# module_af.net
KiCad netlist of a schematic drawn in EAGLE
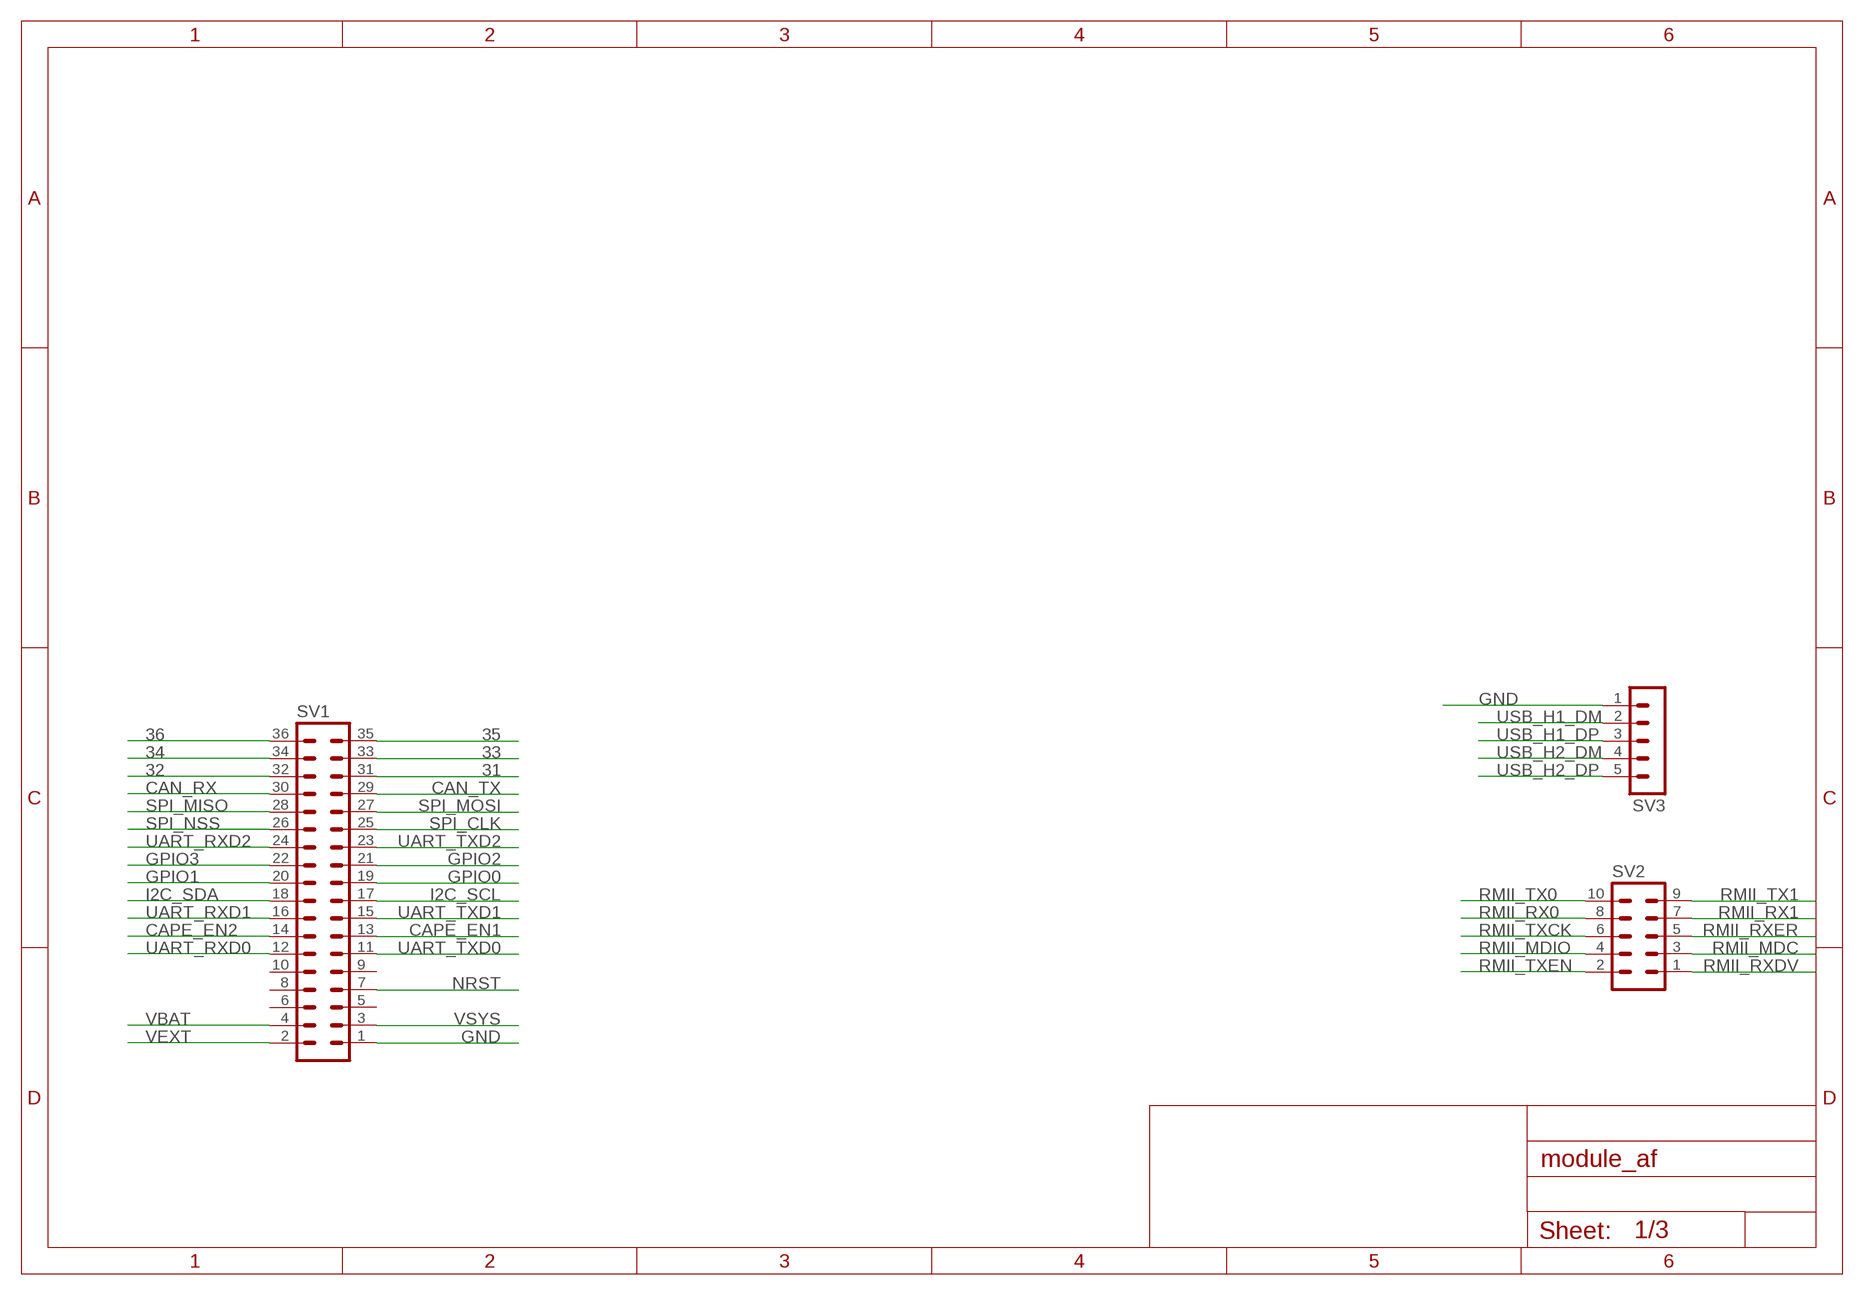
[diagram p0: schematic, sheet 1]
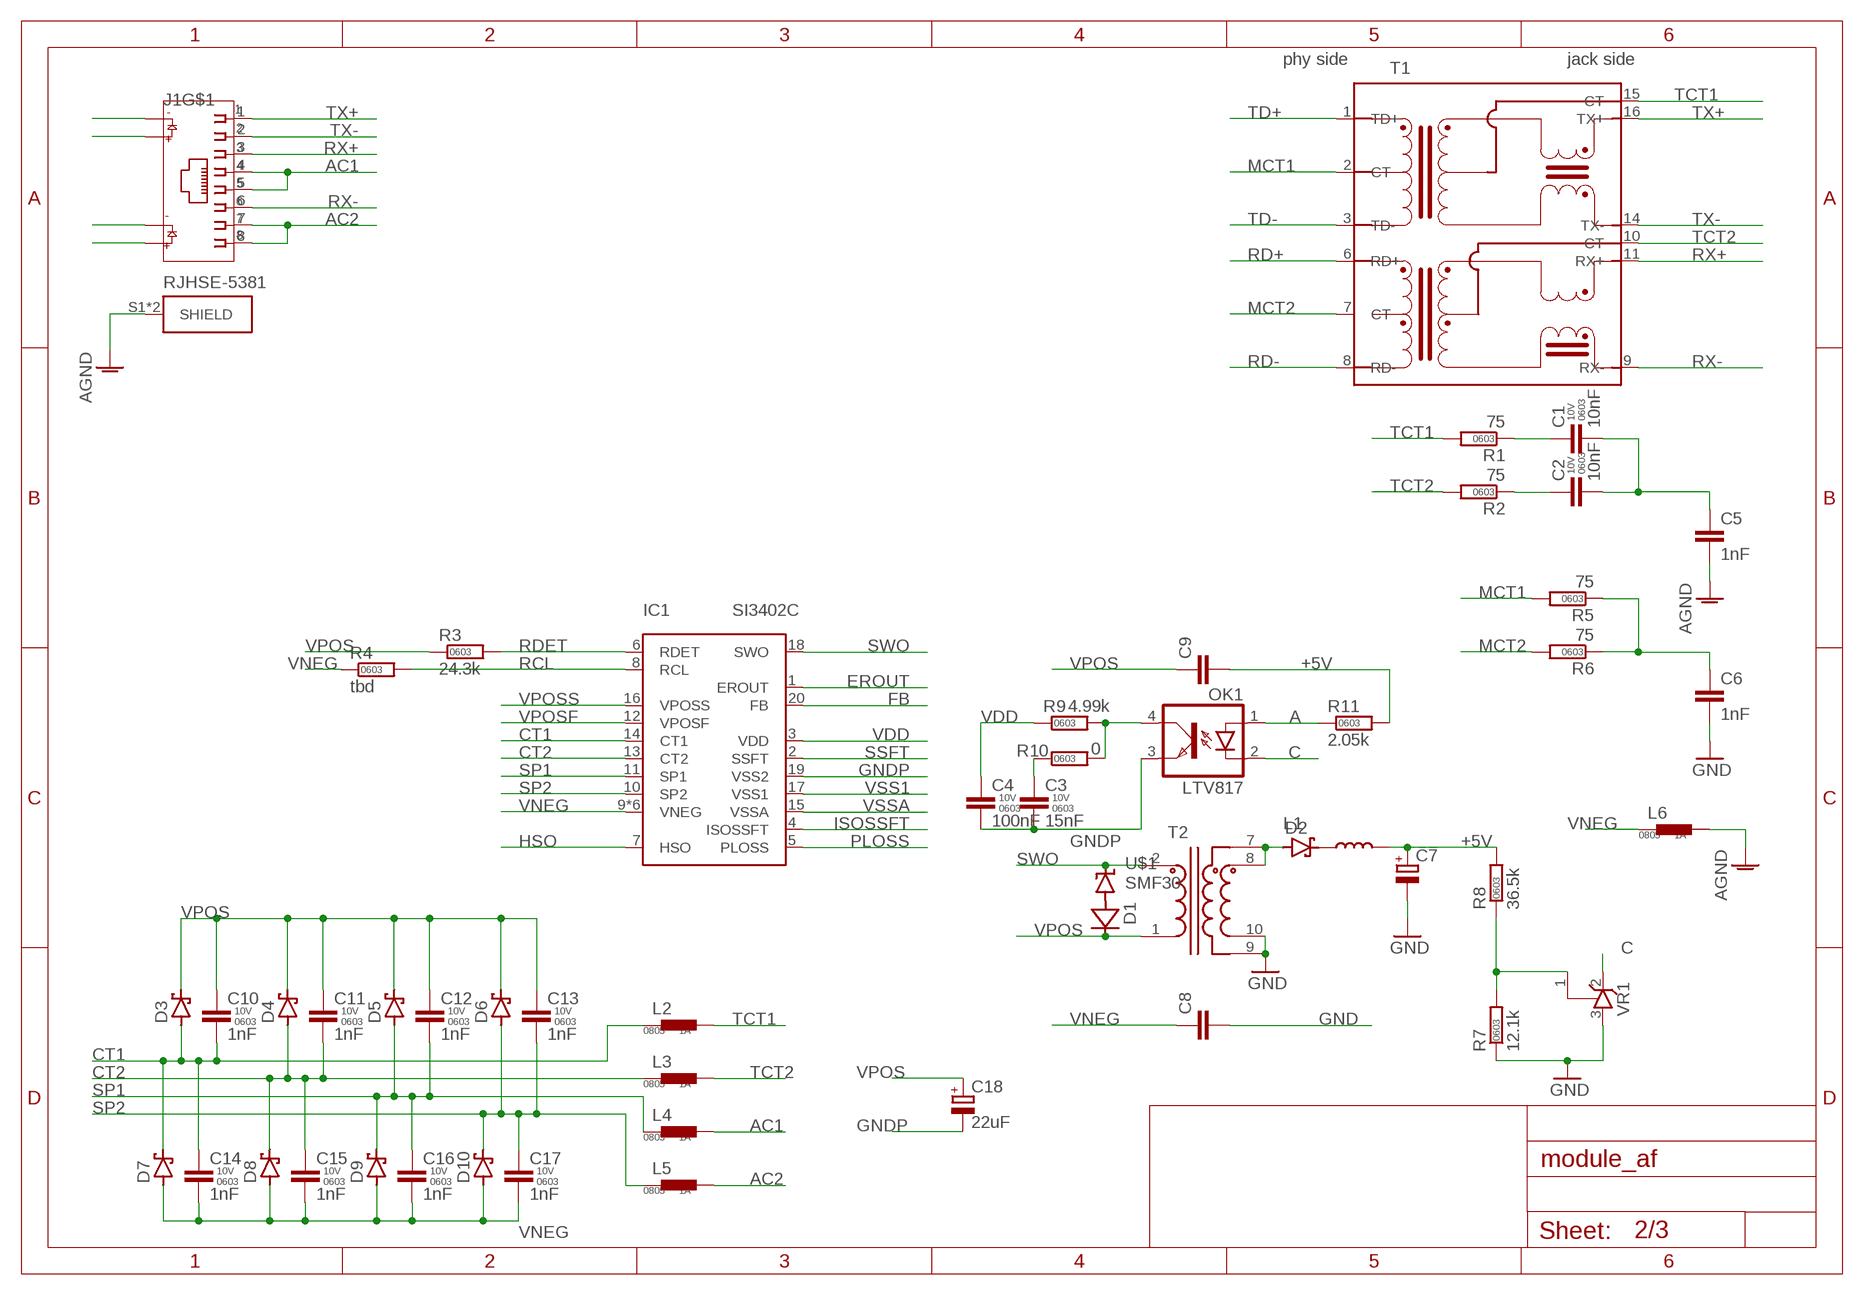
[diagram p1: schematic, sheet 2]
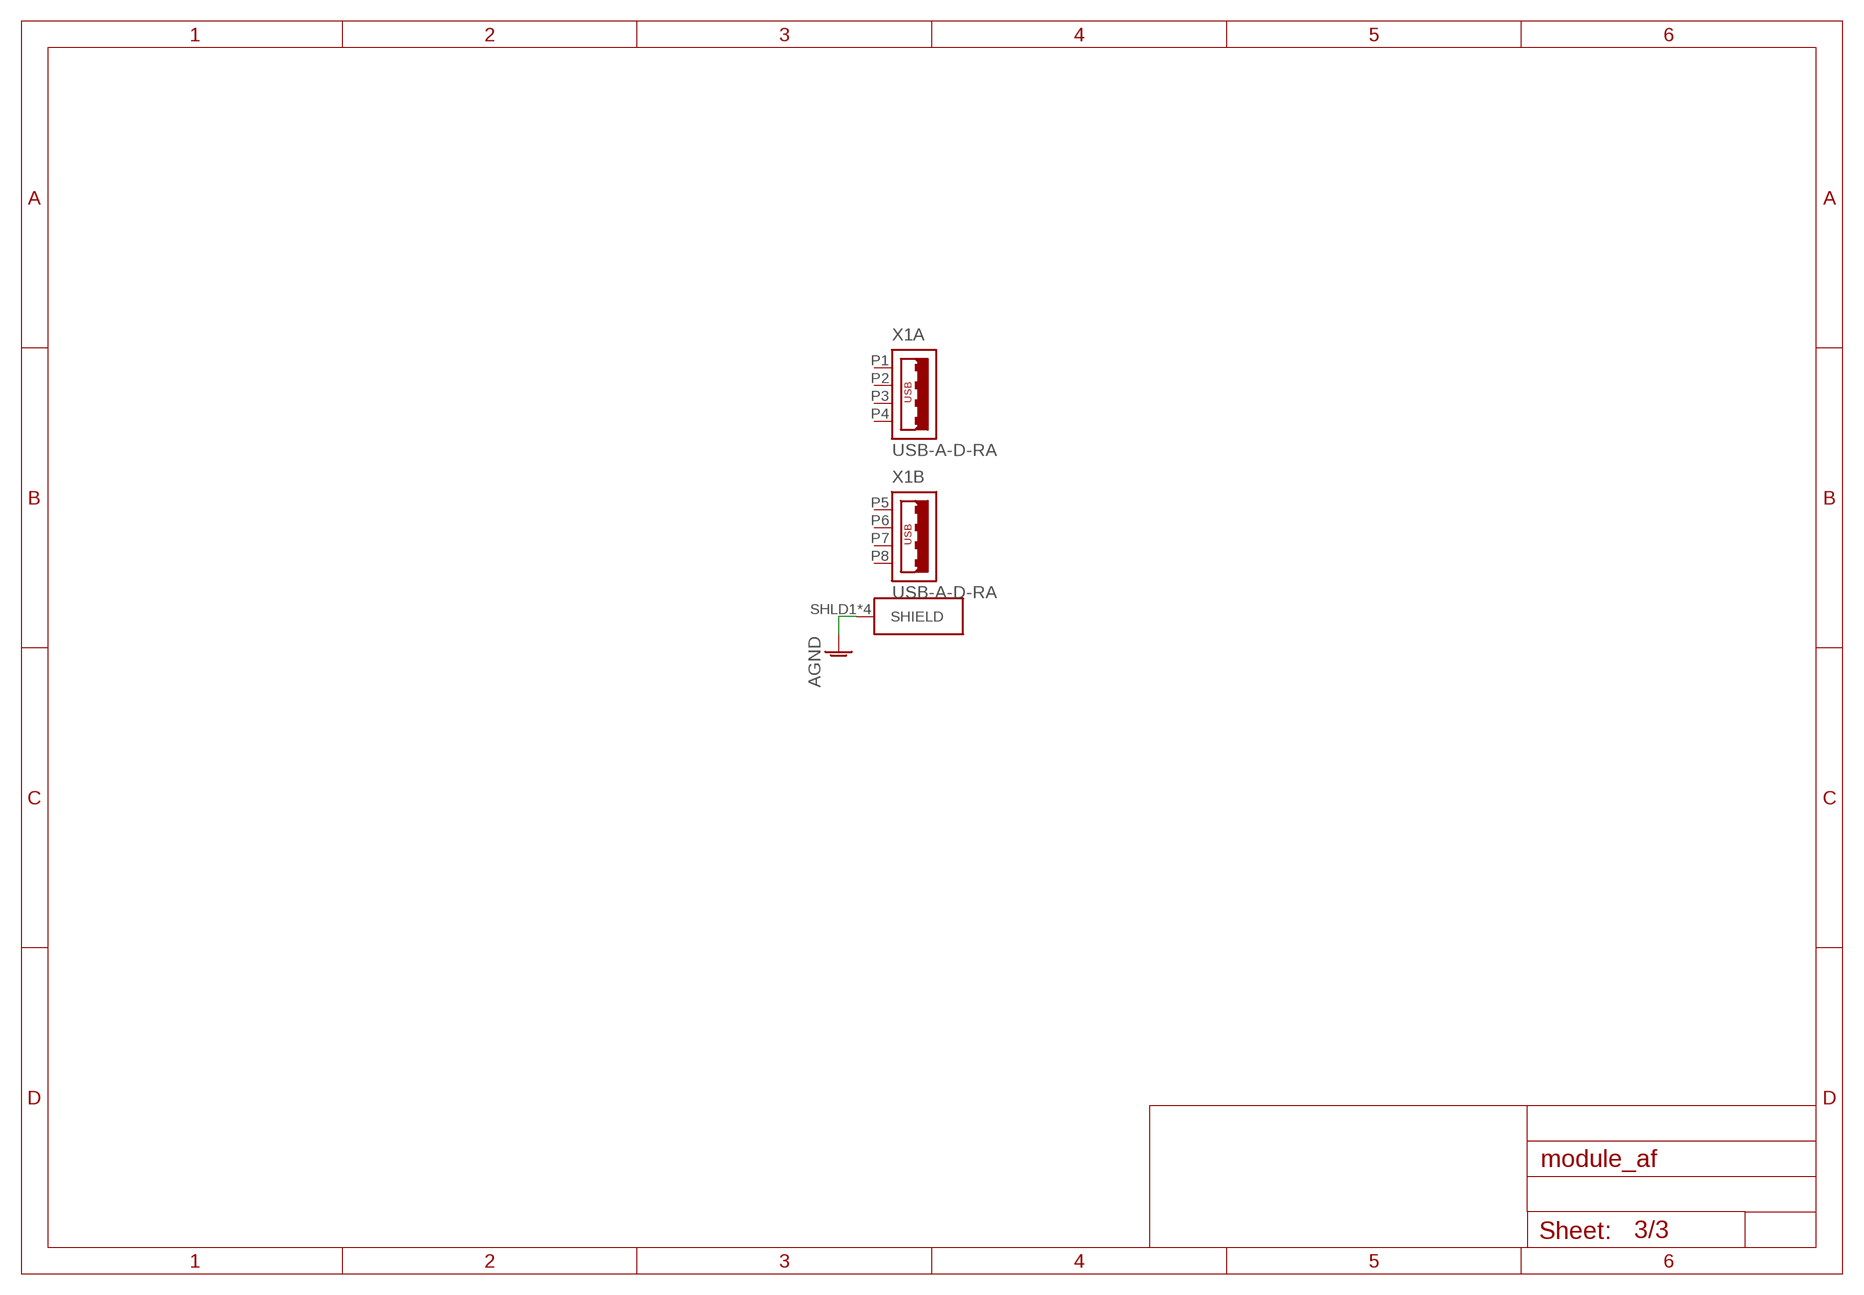
[diagram p2: schematic, sheet 3]

(export (version "E")
  (design (tool "Eeschema 10.0.6"))
  (components
    (comp (ref "X1")
      (value "USB-A-D-RA")
      (footprint "eagle-import:DS1096")
      (libsource (lib "eagle-import") (part "USB_2P-"))
    )
    (comp (ref "C1")
      (value "10nF")
      (footprint "eagle-import:C0603")
      (fields (field (name "RATING") "10V") (field (name "PACKAGE") "0603"))
      (libsource (lib "eagle-import") (part "CAP-0603"))
    )
    (comp (ref "C2")
      (value "10nF")
      (footprint "eagle-import:C0603")
      (fields (field (name "RATING") "10V") (field (name "PACKAGE") "0603"))
      (libsource (lib "eagle-import") (part "CAP-0603"))
    )
    (comp (ref "C3")
      (value "15nF")
      (footprint "eagle-import:C0603")
      (fields (field (name "RATING") "10V") (field (name "PACKAGE") "0603"))
      (libsource (lib "eagle-import") (part "CAP-0603"))
    )
    (comp (ref "C4")
      (value "100nF")
      (footprint "eagle-import:C0603")
      (fields (field (name "RATING") "10V") (field (name "PACKAGE") "0603"))
      (libsource (lib "eagle-import") (part "CAP-0603"))
    )
    (comp (ref "C5")
      (value "1nF")
      (footprint "eagle-import:C1206")
      (libsource (lib "eagle-import") (part "C-EUC1206"))
    )
    (comp (ref "C6")
      (value "1nF")
      (footprint "eagle-import:C1206")
      (libsource (lib "eagle-import") (part "C-EUC1206"))
    )
    (comp (ref "C7")
      (value "CPOL-EUE5-10.5")
      (footprint "eagle-import:E5-10,5")
      (libsource (lib "eagle-import") (part "CPOL-EUE5-10.5"))
    )
    (comp (ref "C8")
      (value "CAP-075-032X103")
      (footprint "eagle-import:C075-032X103")
      (libsource (lib "eagle-import") (part "CAP-075-032X103"))
    )
    (comp (ref "C9")
      (value "CAP-075-032X103")
      (footprint "eagle-import:C075-032X103")
      (libsource (lib "eagle-import") (part "CAP-075-032X103"))
    )
    (comp (ref "C10")
      (value "1nF")
      (footprint "eagle-import:C0603")
      (fields (field (name "RATING") "10V") (field (name "PACKAGE") "0603"))
      (libsource (lib "eagle-import") (part "CAP-0603"))
    )
    (comp (ref "C11")
      (value "1nF")
      (footprint "eagle-import:C0603")
      (fields (field (name "RATING") "10V") (field (name "PACKAGE") "0603"))
      (libsource (lib "eagle-import") (part "CAP-0603"))
    )
    (comp (ref "C12")
      (value "1nF")
      (footprint "eagle-import:C0603")
      (fields (field (name "RATING") "10V") (field (name "PACKAGE") "0603"))
      (libsource (lib "eagle-import") (part "CAP-0603"))
    )
    (comp (ref "C13")
      (value "1nF")
      (footprint "eagle-import:C0603")
      (fields (field (name "RATING") "10V") (field (name "PACKAGE") "0603"))
      (libsource (lib "eagle-import") (part "CAP-0603"))
    )
    (comp (ref "C14")
      (value "1nF")
      (footprint "eagle-import:C0603")
      (fields (field (name "RATING") "10V") (field (name "PACKAGE") "0603"))
      (libsource (lib "eagle-import") (part "CAP-0603"))
    )
    (comp (ref "C15")
      (value "1nF")
      (footprint "eagle-import:C0603")
      (fields (field (name "RATING") "10V") (field (name "PACKAGE") "0603"))
      (libsource (lib "eagle-import") (part "CAP-0603"))
    )
    (comp (ref "C16")
      (value "1nF")
      (footprint "eagle-import:C0603")
      (fields (field (name "RATING") "10V") (field (name "PACKAGE") "0603"))
      (libsource (lib "eagle-import") (part "CAP-0603"))
    )
    (comp (ref "C17")
      (value "1nF")
      (footprint "eagle-import:C0603")
      (fields (field (name "RATING") "10V") (field (name "PACKAGE") "0603"))
      (libsource (lib "eagle-import") (part "CAP-0603"))
    )
    (comp (ref "C18")
      (value "22uF")
      (footprint "eagle-import:E3,5-8")
      (libsource (lib "eagle-import") (part "CPOL-EUE3.5-8"))
    )
    (comp (ref "D1")
      (value "1N4148WS")
      (footprint "eagle-import:SOD323")
      (libsource (lib "eagle-import") (part "1N4148WS"))
    )
    (comp (ref "D2")
      (value "SCHOTTKY-DIODESMC")
      (footprint "eagle-import:SMC")
      (libsource (lib "eagle-import") (part "SCHOTTKY-DIODESMC"))
    )
    (comp (ref "D3")
      (value "SK110")
      (footprint "eagle-import:DO214AC")
      (libsource (lib "eagle-import") (part "SK110"))
    )
    (comp (ref "D4")
      (value "SK110")
      (footprint "eagle-import:DO214AC")
      (libsource (lib "eagle-import") (part "SK110"))
    )
    (comp (ref "D5")
      (value "SK110")
      (footprint "eagle-import:DO214AC")
      (libsource (lib "eagle-import") (part "SK110"))
    )
    (comp (ref "D6")
      (value "SK110")
      (footprint "eagle-import:DO214AC")
      (libsource (lib "eagle-import") (part "SK110"))
    )
    (comp (ref "D7")
      (value "SK110")
      (footprint "eagle-import:DO214AC")
      (libsource (lib "eagle-import") (part "SK110"))
    )
    (comp (ref "D8")
      (value "SK110")
      (footprint "eagle-import:DO214AC")
      (libsource (lib "eagle-import") (part "SK110"))
    )
    (comp (ref "D9")
      (value "SK110")
      (footprint "eagle-import:DO214AC")
      (libsource (lib "eagle-import") (part "SK110"))
    )
    (comp (ref "D10")
      (value "SK110")
      (footprint "eagle-import:DO214AC")
      (libsource (lib "eagle-import") (part "SK110"))
    )
    (comp (ref "IC1")
      (value "SI3402-C")
      (footprint "eagle-import:QFN80P500X500X90-21T270")
      (libsource (lib "eagle-import") (part "SI3402-C"))
    )
    (comp (ref "J1")
      (value "RJHSE-5381")
      (footprint "eagle-import:AMPHENOL_RJHSE-5381")
      (fields (field (name "MF") "Amphenol ICC"))
      (libsource (lib "eagle-import") (part "RJHSE-5381"))
    )
    (comp (ref "L1")
      (value "COIL0608-0.022")
      (footprint "eagle-import:COIL0608")
      (libsource (lib "eagle-import") (part "COIL0608-0.022"))
    )
    (comp (ref "L2")
      (value "FER-0805")
      (footprint "eagle-import:FER0805")
      (fields (field (name "PACKAGE") "0805") (field (name "CURRENT") "1A"))
      (libsource (lib "eagle-import") (part "FER-0805"))
    )
    (comp (ref "L3")
      (value "FER-0805")
      (footprint "eagle-import:FER0805")
      (fields (field (name "PACKAGE") "0805") (field (name "CURRENT") "1A"))
      (libsource (lib "eagle-import") (part "FER-0805"))
    )
    (comp (ref "L4")
      (value "FER-0805")
      (footprint "eagle-import:FER0805")
      (fields (field (name "PACKAGE") "0805") (field (name "CURRENT") "1A"))
      (libsource (lib "eagle-import") (part "FER-0805"))
    )
    (comp (ref "L5")
      (value "FER-0805")
      (footprint "eagle-import:FER0805")
      (fields (field (name "PACKAGE") "0805") (field (name "CURRENT") "1A"))
      (libsource (lib "eagle-import") (part "FER-0805"))
    )
    (comp (ref "L6")
      (value "FER-0805")
      (footprint "eagle-import:FER0805")
      (fields (field (name "PACKAGE") "0805") (field (name "CURRENT") "1A"))
      (libsource (lib "eagle-import") (part "FER-0805"))
    )
    (comp (ref "OK1")
      (value "LTV817")
      (footprint "eagle-import:DIL4-SMD")
      (libsource (lib "eagle-import") (part "LTV816S"))
    )
    (comp (ref "R1")
      (value "75")
      (footprint "eagle-import:R0603")
      (fields (field (name "PACKAGE") "0603"))
      (libsource (lib "eagle-import") (part "RES-0603"))
    )
    (comp (ref "R2")
      (value "75")
      (footprint "eagle-import:R0603")
      (fields (field (name "PACKAGE") "0603"))
      (libsource (lib "eagle-import") (part "RES-0603"))
    )
    (comp (ref "R3")
      (value "24.3k")
      (footprint "eagle-import:R0603")
      (fields (field (name "PACKAGE") "0603"))
      (libsource (lib "eagle-import") (part "RES-0603"))
    )
    (comp (ref "R4")
      (value "tbd")
      (footprint "eagle-import:R0603")
      (fields (field (name "PACKAGE") "0603"))
      (libsource (lib "eagle-import") (part "RES-0603"))
    )
    (comp (ref "R5")
      (value "75")
      (footprint "eagle-import:R0603")
      (fields (field (name "PACKAGE") "0603"))
      (libsource (lib "eagle-import") (part "RES-0603"))
    )
    (comp (ref "R6")
      (value "75")
      (footprint "eagle-import:R0603")
      (fields (field (name "PACKAGE") "0603"))
      (libsource (lib "eagle-import") (part "RES-0603"))
    )
    (comp (ref "R7")
      (value "12.1k")
      (footprint "eagle-import:R0603")
      (fields (field (name "PACKAGE") "0603"))
      (libsource (lib "eagle-import") (part "RES-0603"))
    )
    (comp (ref "R8")
      (value "36.5k")
      (footprint "eagle-import:R0603")
      (fields (field (name "PACKAGE") "0603"))
      (libsource (lib "eagle-import") (part "RES-0603"))
    )
    (comp (ref "R9")
      (value "4.99k")
      (footprint "eagle-import:R0603")
      (fields (field (name "PACKAGE") "0603"))
      (libsource (lib "eagle-import") (part "RES-0603"))
    )
    (comp (ref "R10")
      (value "0")
      (footprint "eagle-import:R0603")
      (fields (field (name "PACKAGE") "0603"))
      (libsource (lib "eagle-import") (part "RES-0603"))
    )
    (comp (ref "R11")
      (value "2.05k")
      (footprint "eagle-import:R0603")
      (fields (field (name "PACKAGE") "0603"))
      (libsource (lib "eagle-import") (part "RES-0603"))
    )
    (comp (ref "T1")
      (value "PT61017PEL")
      (footprint "eagle-import:PT61017")
      (libsource (lib "eagle-import") (part "PT61017PEL"))
    )
    (comp (ref "T2")
      (value "FA2805-CL")
      (footprint "eagle-import:FA2")
      (libsource (lib "eagle-import") (part "FA2805-CL"))
    )
    (comp (ref "U$1")
      (value "SMF30")
      (footprint "eagle-import:SODFL3718X130")
      (libsource (lib "eagle-import") (part "SMF30"))
    )
    (comp (ref "VR1")
      (value "TLV431")
      (footprint "eagle-import:SOT95P240X110-3")
      (libsource (lib "eagle-import") (part "TLV431"))
    )
    (comp (ref "SV1")
      (value "MA18-2")
      (footprint "eagle-import:MA18-2")
      (libsource (lib "eagle-import") (part "MA18-2"))
    )
    (comp (ref "SV2")
      (value "MA05-2")
      (footprint "eagle-import:MA05-2")
      (libsource (lib "eagle-import") (part "MA05-2"))
    )
    (comp (ref "SV3")
      (value "MA05-1")
      (footprint "eagle-import:MA05-1")
      (libsource (lib "eagle-import") (part "MA05-1"))
    )
  )
  (nets
    (net (code "1") (name "+5V") (class "Default")
      (node (ref "C7") (pin "+") (pinfunction "+_+") (pintype "passive"))
      (node (ref "C9") (pin "2") (pinfunction "2_2") (pintype "passive"))
      (node (ref "L1") (pin "P$2") (pinfunction "2_P$2") (pintype "passive"))
      (node (ref "R11") (pin "2") (pinfunction "2_2") (pintype "passive"))
      (node (ref "R8") (pin "2") (pinfunction "2_2") (pintype "passive"))
    )
    (net (code "2") (name "31") (class "Default")
      (node (ref "SV1") (pin "31") (pinfunction "31_31") (pintype "passive"))
    )
    (net (code "3") (name "32") (class "Default")
      (node (ref "SV1") (pin "32") (pinfunction "32_32") (pintype "passive"))
    )
    (net (code "4") (name "33") (class "Default")
      (node (ref "SV1") (pin "33") (pinfunction "33_33") (pintype "passive"))
    )
    (net (code "5") (name "34") (class "Default")
      (node (ref "SV1") (pin "34") (pinfunction "34_34") (pintype "passive"))
    )
    (net (code "6") (name "35") (class "Default")
      (node (ref "SV1") (pin "35") (pinfunction "35_35") (pintype "passive"))
    )
    (net (code "7") (name "36") (class "Default")
      (node (ref "SV1") (pin "36") (pinfunction "36_36") (pintype "passive"))
    )
    (net (code "8") (name "A") (class "Default")
      (node (ref "OK1") (pin "1") (pinfunction "A_1") (pintype "passive"))
      (node (ref "R11") (pin "1") (pinfunction "1_1") (pintype "passive"))
    )
    (net (code "9") (name "AC1") (class "Default")
      (node (ref "J1") (pin "4") (pinfunction "4_4") (pintype "passive"))
      (node (ref "J1") (pin "5") (pinfunction "5_5") (pintype "passive"))
      (node (ref "L4") (pin "2") (pinfunction "2_2") (pintype "passive"))
    )
    (net (code "10") (name "AC2") (class "Default")
      (node (ref "J1") (pin "7") (pinfunction "7_7") (pintype "passive"))
      (node (ref "J1") (pin "8") (pinfunction "8_8") (pintype "passive"))
      (node (ref "L5") (pin "2") (pinfunction "2_2") (pintype "passive"))
    )
    (net (code "11") (name "AGND") (class "Default")
      (node (ref "C5") (pin "2") (pinfunction "2_2") (pintype "passive"))
      (node (ref "J1") (pin "S1") (pinfunction "SHIELD_S1") (pintype "bidirectional"))
      (node (ref "J1") (pin "S2") (pinfunction "SHIELD_S2") (pintype "bidirectional"))
      (node (ref "L6") (pin "2") (pinfunction "2_2") (pintype "passive"))
      (node (ref "X1") (pin "SHLD1") (pinfunction "SHIELD_SHLD1") (pintype "bidirectional"))
      (node (ref "X1") (pin "SHLD2") (pinfunction "SHIELD_SHLD2") (pintype "bidirectional"))
      (node (ref "X1") (pin "SHLD3") (pinfunction "SHIELD_SHLD3") (pintype "bidirectional"))
      (node (ref "X1") (pin "SHLD4") (pinfunction "SHIELD_SHLD4") (pintype "bidirectional"))
    )
    (net (code "12") (name "C") (class "Default")
      (node (ref "OK1") (pin "2") (pinfunction "C_2") (pintype "passive"))
      (node (ref "VR1") (pin "2") (pinfunction "C_2") (pintype "passive"))
    )
    (net (code "13") (name "CAN_RX") (class "Default")
      (node (ref "SV1") (pin "30") (pinfunction "30_30") (pintype "passive"))
    )
    (net (code "14") (name "CAN_TX") (class "Default")
      (node (ref "SV1") (pin "29") (pinfunction "29_29") (pintype "passive"))
    )
    (net (code "15") (name "CAPE_EN1") (class "Default")
      (node (ref "SV1") (pin "13") (pinfunction "13_13") (pintype "passive"))
    )
    (net (code "16") (name "CAPE_EN2") (class "Default")
      (node (ref "SV1") (pin "14") (pinfunction "14_14") (pintype "passive"))
    )
    (net (code "17") (name "CT1") (class "Default")
      (node (ref "C10") (pin "2") (pinfunction "2_2") (pintype "passive"))
      (node (ref "C14") (pin "1") (pinfunction "1_1") (pintype "passive"))
      (node (ref "D3") (pin "A") (pinfunction "A_A") (pintype "passive"))
      (node (ref "D7") (pin "C") (pinfunction "C_C") (pintype "passive"))
      (node (ref "IC1") (pin "14") (pinfunction "CT1_14") (pintype "bidirectional"))
      (node (ref "L2") (pin "1") (pinfunction "1_1") (pintype "passive"))
    )
    (net (code "18") (name "CT2") (class "Default")
      (node (ref "C11") (pin "2") (pinfunction "2_2") (pintype "passive"))
      (node (ref "C15") (pin "1") (pinfunction "1_1") (pintype "passive"))
      (node (ref "D4") (pin "A") (pinfunction "A_A") (pintype "passive"))
      (node (ref "D8") (pin "C") (pinfunction "C_C") (pintype "passive"))
      (node (ref "IC1") (pin "13") (pinfunction "CT2_13") (pintype "bidirectional"))
      (node (ref "L3") (pin "1") (pinfunction "1_1") (pintype "passive"))
    )
    (net (code "19") (name "EROUT") (class "Default")
      (node (ref "IC1") (pin "1") (pinfunction "EROUT_1") (pintype "bidirectional"))
    )
    (net (code "20") (name "FB") (class "Default")
      (node (ref "IC1") (pin "20") (pinfunction "FB_20") (pintype "bidirectional"))
    )
    (net (code "21") (name "GND") (class "Default")
      (node (ref "C6") (pin "2") (pinfunction "2_2") (pintype "passive"))
      (node (ref "C7") (pin "-") (pinfunction "-_-") (pintype "passive"))
      (node (ref "C8") (pin "2") (pinfunction "2_2") (pintype "passive"))
      (node (ref "R7") (pin "1") (pinfunction "1_1") (pintype "passive"))
      (node (ref "SV1") (pin "1") (pinfunction "1_1") (pintype "passive"))
      (node (ref "SV3") (pin "1") (pinfunction "1_1") (pintype "passive"))
      (node (ref "T2") (pin "10") (pinfunction "10_10") (pintype "bidirectional"))
      (node (ref "T2") (pin "9") (pinfunction "9_9") (pintype "bidirectional"))
      (node (ref "VR1") (pin "3") (pinfunction "A_3") (pintype "passive"))
    )
    (net (code "22") (name "GNDP") (class "Default")
      (node (ref "C18") (pin "-") (pinfunction "-_-") (pintype "passive"))
      (node (ref "C3") (pin "2") (pinfunction "2_2") (pintype "passive"))
      (node (ref "C4") (pin "2") (pinfunction "2_2") (pintype "passive"))
      (node (ref "IC1") (pin "19") (pinfunction "VSS2_19") (pintype "bidirectional"))
      (node (ref "OK1") (pin "3") (pinfunction "EMIT_3") (pintype "passive"))
    )
    (net (code "23") (name "GPIO0") (class "Default")
      (node (ref "SV1") (pin "19") (pinfunction "19_19") (pintype "passive"))
    )
    (net (code "24") (name "GPIO1") (class "Default")
      (node (ref "SV1") (pin "20") (pinfunction "20_20") (pintype "passive"))
    )
    (net (code "25") (name "GPIO2") (class "Default")
      (node (ref "SV1") (pin "21") (pinfunction "21_21") (pintype "passive"))
    )
    (net (code "26") (name "GPIO3") (class "Default")
      (node (ref "SV1") (pin "22") (pinfunction "22_22") (pintype "passive"))
    )
    (net (code "27") (name "HSO") (class "Default")
      (node (ref "IC1") (pin "7") (pinfunction "HSO_7") (pintype "bidirectional"))
    )
    (net (code "28") (name "I2C_SCL") (class "Default")
      (node (ref "SV1") (pin "17") (pinfunction "17_17") (pintype "passive"))
    )
    (net (code "29") (name "I2C_SDA") (class "Default")
      (node (ref "SV1") (pin "18") (pinfunction "18_18") (pintype "passive"))
    )
    (net (code "30") (name "ISOSSFT") (class "Default")
      (node (ref "IC1") (pin "4") (pinfunction "ISOSSFT_4") (pintype "bidirectional"))
    )
    (net (code "31") (name "MCT1") (class "Default")
      (node (ref "R5") (pin "2") (pinfunction "2_2") (pintype "passive"))
      (node (ref "T1") (pin "2") (pinfunction "CT_2") (pintype "bidirectional"))
    )
    (net (code "32") (name "MCT2") (class "Default")
      (node (ref "R6") (pin "2") (pinfunction "2_2") (pintype "passive"))
      (node (ref "T1") (pin "7") (pinfunction "CT_7") (pintype "bidirectional"))
    )
    (net (code "33") (name "NRST") (class "Default")
      (node (ref "SV1") (pin "7") (pinfunction "7_7") (pintype "passive"))
    )
    (net (code "34") (name "Net-(C1-Pad1)") (class "Default")
      (node (ref "C1") (pin "1") (pinfunction "1_1") (pintype "passive"))
      (node (ref "R1") (pin "1") (pinfunction "1_1") (pintype "passive"))
    )
    (net (code "35") (name "Net-(C1-Pad2)") (class "Default")
      (node (ref "C1") (pin "2") (pinfunction "2_2") (pintype "passive"))
      (node (ref "C2") (pin "2") (pinfunction "2_2") (pintype "passive"))
      (node (ref "C5") (pin "1") (pinfunction "1_1") (pintype "passive"))
    )
    (net (code "36") (name "Net-(C2-Pad1)") (class "Default")
      (node (ref "C2") (pin "1") (pinfunction "1_1") (pintype "passive"))
      (node (ref "R2") (pin "1") (pinfunction "1_1") (pintype "passive"))
    )
    (net (code "37") (name "Net-(C3-Pad1)") (class "Default")
      (node (ref "C3") (pin "1") (pinfunction "1_1") (pintype "passive"))
      (node (ref "R10") (pin "1") (pinfunction "1_1") (pintype "passive"))
    )
    (net (code "38") (name "Net-(C6-Pad1)") (class "Default")
      (node (ref "C6") (pin "1") (pinfunction "1_1") (pintype "passive"))
      (node (ref "R5") (pin "1") (pinfunction "1_1") (pintype "passive"))
      (node (ref "R6") (pin "1") (pinfunction "1_1") (pintype "passive"))
    )
    (net (code "39") (name "Net-(D1-PadA)") (class "Default")
      (node (ref "D1") (pin "A") (pinfunction "A_A") (pintype "passive"))
      (node (ref "U$1") (pin "A") (pinfunction "A_A") (pintype "passive"))
    )
    (net (code "40") (name "Net-(D2-PadA)") (class "Default")
      (node (ref "D2") (pin "A") (pinfunction "A_A") (pintype "passive"))
      (node (ref "T2") (pin "7") (pinfunction "7_7") (pintype "bidirectional"))
      (node (ref "T2") (pin "8") (pinfunction "8_8") (pintype "bidirectional"))
    )
    (net (code "41") (name "Net-(L1-1)") (class "Default")
      (node (ref "D2") (pin "C") (pinfunction "C_C") (pintype "passive"))
      (node (ref "L1") (pin "P$1") (pinfunction "1_P$1") (pintype "passive"))
    )
    (net (code "42") (name "Net-(OK1-COL)") (class "Default")
      (node (ref "OK1") (pin "4") (pinfunction "COL_4") (pintype "passive"))
      (node (ref "R10") (pin "2") (pinfunction "2_2") (pintype "passive"))
      (node (ref "R9") (pin "2") (pinfunction "2_2") (pintype "passive"))
    )
    (net (code "43") (name "Net-(VR1-R)") (class "Default")
      (node (ref "R7") (pin "2") (pinfunction "2_2") (pintype "passive"))
      (node (ref "R8") (pin "1") (pinfunction "1_1") (pintype "passive"))
      (node (ref "VR1") (pin "1") (pinfunction "R_1") (pintype "passive"))
    )
    (net (code "44") (name "PLOSS") (class "Default")
      (node (ref "IC1") (pin "5") (pinfunction "PLOSS_5") (pintype "bidirectional"))
    )
    (net (code "45") (name "RCL") (class "Default")
      (node (ref "IC1") (pin "8") (pinfunction "RCL_8") (pintype "bidirectional"))
      (node (ref "R4") (pin "2") (pinfunction "2_2") (pintype "passive"))
    )
    (net (code "46") (name "RD+") (class "Default")
      (node (ref "T1") (pin "6") (pinfunction "RD+_6") (pintype "bidirectional"))
    )
    (net (code "47") (name "RD-") (class "Default")
      (node (ref "T1") (pin "8") (pinfunction "RD-_8") (pintype "bidirectional"))
    )
    (net (code "48") (name "RDET") (class "Default")
      (node (ref "IC1") (pin "6") (pinfunction "RDET_6") (pintype "bidirectional"))
      (node (ref "R3") (pin "2") (pinfunction "2_2") (pintype "passive"))
    )
    (net (code "49") (name "RMII_MDC") (class "Default")
      (node (ref "SV2") (pin "3") (pinfunction "3_3") (pintype "passive"))
    )
    (net (code "50") (name "RMII_MDIO") (class "Default")
      (node (ref "SV2") (pin "4") (pinfunction "4_4") (pintype "passive"))
    )
    (net (code "51") (name "RMII_RX0") (class "Default")
      (node (ref "SV2") (pin "8") (pinfunction "8_8") (pintype "passive"))
    )
    (net (code "52") (name "RMII_RX1") (class "Default")
      (node (ref "SV2") (pin "7") (pinfunction "7_7") (pintype "passive"))
    )
    (net (code "53") (name "RMII_RXDV") (class "Default")
      (node (ref "SV2") (pin "1") (pinfunction "1_1") (pintype "passive"))
    )
    (net (code "54") (name "RMII_RXER") (class "Default")
      (node (ref "SV2") (pin "5") (pinfunction "5_5") (pintype "passive"))
    )
    (net (code "55") (name "RMII_TX0") (class "Default")
      (node (ref "SV2") (pin "10") (pinfunction "10_10") (pintype "passive"))
    )
    (net (code "56") (name "RMII_TX1") (class "Default")
      (node (ref "SV2") (pin "9") (pinfunction "9_9") (pintype "passive"))
    )
    (net (code "57") (name "RMII_TXCK") (class "Default")
      (node (ref "SV2") (pin "6") (pinfunction "6_6") (pintype "passive"))
    )
    (net (code "58") (name "RMII_TXEN") (class "Default")
      (node (ref "SV2") (pin "2") (pinfunction "2_2") (pintype "passive"))
    )
    (net (code "59") (name "RX+") (class "Default")
      (node (ref "J1") (pin "3") (pinfunction "3_3") (pintype "passive"))
      (node (ref "T1") (pin "11") (pinfunction "RX+_11") (pintype "bidirectional"))
    )
    (net (code "60") (name "RX-") (class "Default")
      (node (ref "J1") (pin "6") (pinfunction "6_6") (pintype "passive"))
      (node (ref "T1") (pin "9") (pinfunction "RX-_9") (pintype "bidirectional"))
    )
    (net (code "61") (name "SP1") (class "Default")
      (node (ref "C12") (pin "2") (pinfunction "2_2") (pintype "passive"))
      (node (ref "C16") (pin "1") (pinfunction "1_1") (pintype "passive"))
      (node (ref "D5") (pin "A") (pinfunction "A_A") (pintype "passive"))
      (node (ref "D9") (pin "C") (pinfunction "C_C") (pintype "passive"))
      (node (ref "IC1") (pin "11") (pinfunction "SP1_11") (pintype "bidirectional"))
      (node (ref "L4") (pin "1") (pinfunction "1_1") (pintype "passive"))
    )
    (net (code "62") (name "SP2") (class "Default")
      (node (ref "C13") (pin "2") (pinfunction "2_2") (pintype "passive"))
      (node (ref "C17") (pin "1") (pinfunction "1_1") (pintype "passive"))
      (node (ref "D10") (pin "C") (pinfunction "C_C") (pintype "passive"))
      (node (ref "D6") (pin "A") (pinfunction "A_A") (pintype "passive"))
      (node (ref "IC1") (pin "10") (pinfunction "SP2_10") (pintype "bidirectional"))
      (node (ref "L5") (pin "1") (pinfunction "1_1") (pintype "passive"))
    )
    (net (code "63") (name "SPI_CLK") (class "Default")
      (node (ref "SV1") (pin "25") (pinfunction "25_25") (pintype "passive"))
    )
    (net (code "64") (name "SPI_MISO") (class "Default")
      (node (ref "SV1") (pin "28") (pinfunction "28_28") (pintype "passive"))
    )
    (net (code "65") (name "SPI_MOSI") (class "Default")
      (node (ref "SV1") (pin "27") (pinfunction "27_27") (pintype "passive"))
    )
    (net (code "66") (name "SPI_NSS") (class "Default")
      (node (ref "SV1") (pin "26") (pinfunction "26_26") (pintype "passive"))
    )
    (net (code "67") (name "SSFT") (class "Default")
      (node (ref "IC1") (pin "2") (pinfunction "SSFT_2") (pintype "bidirectional"))
    )
    (net (code "68") (name "SWO") (class "Default")
      (node (ref "IC1") (pin "18") (pinfunction "SWO_18") (pintype "bidirectional"))
      (node (ref "T2") (pin "2") (pinfunction "2_2") (pintype "bidirectional"))
      (node (ref "U$1") (pin "C") (pinfunction "C_C") (pintype "passive"))
    )
    (net (code "69") (name "TCT1") (class "Default")
      (node (ref "L2") (pin "2") (pinfunction "2_2") (pintype "passive"))
      (node (ref "R1") (pin "2") (pinfunction "2_2") (pintype "passive"))
      (node (ref "T1") (pin "15") (pinfunction "CT_15") (pintype "bidirectional"))
    )
    (net (code "70") (name "TCT2") (class "Default")
      (node (ref "L3") (pin "2") (pinfunction "2_2") (pintype "passive"))
      (node (ref "R2") (pin "2") (pinfunction "2_2") (pintype "passive"))
      (node (ref "T1") (pin "10") (pinfunction "CT_10") (pintype "bidirectional"))
    )
    (net (code "71") (name "TD+") (class "Default")
      (node (ref "T1") (pin "1") (pinfunction "TD+_1") (pintype "bidirectional"))
    )
    (net (code "72") (name "TD-") (class "Default")
      (node (ref "T1") (pin "3") (pinfunction "TD-_3") (pintype "bidirectional"))
    )
    (net (code "73") (name "TX+") (class "Default")
      (node (ref "J1") (pin "1") (pinfunction "1_1") (pintype "passive"))
      (node (ref "T1") (pin "16") (pinfunction "TX+_16") (pintype "bidirectional"))
    )
    (net (code "74") (name "TX-") (class "Default")
      (node (ref "J1") (pin "2") (pinfunction "2_2") (pintype "passive"))
      (node (ref "T1") (pin "14") (pinfunction "TX-_14") (pintype "bidirectional"))
    )
    (net (code "75") (name "UART_RXD0") (class "Default")
      (node (ref "SV1") (pin "12") (pinfunction "12_12") (pintype "passive"))
    )
    (net (code "76") (name "UART_RXD1") (class "Default")
      (node (ref "SV1") (pin "16") (pinfunction "16_16") (pintype "passive"))
    )
    (net (code "77") (name "UART_RXD2") (class "Default")
      (node (ref "SV1") (pin "24") (pinfunction "24_24") (pintype "passive"))
    )
    (net (code "78") (name "UART_TXD0") (class "Default")
      (node (ref "SV1") (pin "11") (pinfunction "11_11") (pintype "passive"))
    )
    (net (code "79") (name "UART_TXD1") (class "Default")
      (node (ref "SV1") (pin "15") (pinfunction "15_15") (pintype "passive"))
    )
    (net (code "80") (name "UART_TXD2") (class "Default")
      (node (ref "SV1") (pin "23") (pinfunction "23_23") (pintype "passive"))
    )
    (net (code "81") (name "USB_H1_DM") (class "Default")
      (node (ref "SV3") (pin "2") (pinfunction "2_2") (pintype "passive"))
    )
    (net (code "82") (name "USB_H1_DP") (class "Default")
      (node (ref "SV3") (pin "3") (pinfunction "3_3") (pintype "passive"))
    )
    (net (code "83") (name "USB_H2_DM") (class "Default")
      (node (ref "SV3") (pin "4") (pinfunction "4_4") (pintype "passive"))
    )
    (net (code "84") (name "USB_H2_DP") (class "Default")
      (node (ref "SV3") (pin "5") (pinfunction "5_5") (pintype "passive"))
    )
    (net (code "85") (name "VBAT") (class "Default")
      (node (ref "SV1") (pin "4") (pinfunction "4_4") (pintype "passive"))
    )
    (net (code "86") (name "VDD") (class "Default")
      (node (ref "C4") (pin "1") (pinfunction "1_1") (pintype "passive"))
      (node (ref "IC1") (pin "3") (pinfunction "VDD_3") (pintype "bidirectional"))
      (node (ref "R9") (pin "1") (pinfunction "1_1") (pintype "passive"))
    )
    (net (code "87") (name "VEXT") (class "Default")
      (node (ref "SV1") (pin "2") (pinfunction "2_2") (pintype "passive"))
    )
    (net (code "88") (name "VNEG") (class "Default")
      (node (ref "C14") (pin "2") (pinfunction "2_2") (pintype "passive"))
      (node (ref "C15") (pin "2") (pinfunction "2_2") (pintype "passive"))
      (node (ref "C16") (pin "2") (pinfunction "2_2") (pintype "passive"))
      (node (ref "C17") (pin "2") (pinfunction "2_2") (pintype "passive"))
      (node (ref "C8") (pin "1") (pinfunction "1_1") (pintype "passive"))
      (node (ref "D10") (pin "A") (pinfunction "A_A") (pintype "passive"))
      (node (ref "D7") (pin "A") (pinfunction "A_A") (pintype "passive"))
      (node (ref "D8") (pin "A") (pinfunction "A_A") (pintype "passive"))
      (node (ref "D9") (pin "A") (pinfunction "A_A") (pintype "passive"))
      (node (ref "IC1") (pin "21") (pinfunction "VNEG_21") (pintype "bidirectional"))
      (node (ref "IC1") (pin "9") (pinfunction "VNEG_9") (pintype "bidirectional"))
      (node (ref "IC1") (pin "P$1") (pinfunction "VNEG_P$1") (pintype "bidirectional"))
      (node (ref "IC1") (pin "P$2") (pinfunction "VNEG_P$2") (pintype "bidirectional"))
      (node (ref "IC1") (pin "P$3") (pinfunction "VNEG_P$3") (pintype "bidirectional"))
      (node (ref "IC1") (pin "P$4") (pinfunction "VNEG_P$4") (pintype "bidirectional"))
      (node (ref "L6") (pin "1") (pinfunction "1_1") (pintype "passive"))
      (node (ref "R4") (pin "1") (pinfunction "1_1") (pintype "passive"))
    )
    (net (code "89") (name "VPOS") (class "Default")
      (node (ref "C10") (pin "1") (pinfunction "1_1") (pintype "passive"))
      (node (ref "C11") (pin "1") (pinfunction "1_1") (pintype "passive"))
      (node (ref "C12") (pin "1") (pinfunction "1_1") (pintype "passive"))
      (node (ref "C13") (pin "1") (pinfunction "1_1") (pintype "passive"))
      (node (ref "C18") (pin "+") (pinfunction "+_+") (pintype "passive"))
      (node (ref "C9") (pin "1") (pinfunction "1_1") (pintype "passive"))
      (node (ref "D1") (pin "K") (pinfunction "C_K") (pintype "passive"))
      (node (ref "D3") (pin "C") (pinfunction "C_C") (pintype "passive"))
      (node (ref "D4") (pin "C") (pinfunction "C_C") (pintype "passive"))
      (node (ref "D5") (pin "C") (pinfunction "C_C") (pintype "passive"))
      (node (ref "D6") (pin "C") (pinfunction "C_C") (pintype "passive"))
      (node (ref "R3") (pin "1") (pinfunction "1_1") (pintype "passive"))
      (node (ref "T2") (pin "1") (pinfunction "1_1") (pintype "bidirectional"))
    )
    (net (code "90") (name "VPOSF") (class "Default")
      (node (ref "IC1") (pin "12") (pinfunction "VPOSF_12") (pintype "bidirectional"))
    )
    (net (code "91") (name "VPOSS") (class "Default")
      (node (ref "IC1") (pin "16") (pinfunction "VPOSS_16") (pintype "bidirectional"))
    )
    (net (code "92") (name "VSS1") (class "Default")
      (node (ref "IC1") (pin "17") (pinfunction "VSS1_17") (pintype "bidirectional"))
    )
    (net (code "93") (name "VSSA") (class "Default")
      (node (ref "IC1") (pin "15") (pinfunction "VSSA_15") (pintype "bidirectional"))
    )
    (net (code "94") (name "VSYS") (class "Default")
      (node (ref "SV1") (pin "3") (pinfunction "3_3") (pintype "passive"))
    )
    (net (code "95") (name "unconnected-(J1-Pad9)") (class "Default")
      (node (ref "J1") (pin "9") (pinfunction "9_9") (pintype "passive"))
    )
    (net (code "96") (name "unconnected-(J1-Pad10)") (class "Default")
      (node (ref "J1") (pin "10") (pinfunction "10_10") (pintype "passive"))
    )
    (net (code "97") (name "unconnected-(J1-Pad11)") (class "Default")
      (node (ref "J1") (pin "11") (pinfunction "11_11") (pintype "passive"))
    )
    (net (code "98") (name "unconnected-(J1-Pad12)") (class "Default")
      (node (ref "J1") (pin "12") (pinfunction "12_12") (pintype "passive"))
    )
    (net (code "99") (name "unconnected-(SV1-Pad5)") (class "Default")
      (node (ref "SV1") (pin "5") (pinfunction "5_5") (pintype "passive"))
    )
    (net (code "100") (name "unconnected-(SV1-Pad6)") (class "Default")
      (node (ref "SV1") (pin "6") (pinfunction "6_6") (pintype "passive"))
    )
    (net (code "101") (name "unconnected-(SV1-Pad8)") (class "Default")
      (node (ref "SV1") (pin "8") (pinfunction "8_8") (pintype "passive"))
    )
    (net (code "102") (name "unconnected-(SV1-Pad9)") (class "Default")
      (node (ref "SV1") (pin "9") (pinfunction "9_9") (pintype "passive"))
    )
    (net (code "103") (name "unconnected-(SV1-Pad10)") (class "Default")
      (node (ref "SV1") (pin "10") (pinfunction "10_10") (pintype "passive"))
    )
    (net (code "104") (name "unconnected-(X1A-1-PadP1)") (class "Default")
      (node (ref "X1") (pin "P1") (pinfunction "1_P1") (pintype "passive"))
    )
    (net (code "105") (name "unconnected-(X1A-2-PadP2)") (class "Default")
      (node (ref "X1") (pin "P2") (pinfunction "2_P2") (pintype "passive"))
    )
    (net (code "106") (name "unconnected-(X1A-3-PadP3)") (class "Default")
      (node (ref "X1") (pin "P3") (pinfunction "3_P3") (pintype "passive"))
    )
    (net (code "107") (name "unconnected-(X1A-4-PadP4)") (class "Default")
      (node (ref "X1") (pin "P4") (pinfunction "4_P4") (pintype "passive"))
    )
    (net (code "108") (name "unconnected-(X1B-1-PadP5)") (class "Default")
      (node (ref "X1") (pin "P5") (pinfunction "1_P5") (pintype "passive"))
    )
    (net (code "109") (name "unconnected-(X1B-2-PadP6)") (class "Default")
      (node (ref "X1") (pin "P6") (pinfunction "2_P6") (pintype "passive"))
    )
    (net (code "110") (name "unconnected-(X1B-3-PadP7)") (class "Default")
      (node (ref "X1") (pin "P7") (pinfunction "3_P7") (pintype "passive"))
    )
    (net (code "111") (name "unconnected-(X1B-4-PadP8)") (class "Default")
      (node (ref "X1") (pin "P8") (pinfunction "4_P8") (pintype "passive"))
    )
  )
)
